# schematic.net
KiCad netlist of a schematic drawn in Altium Designer
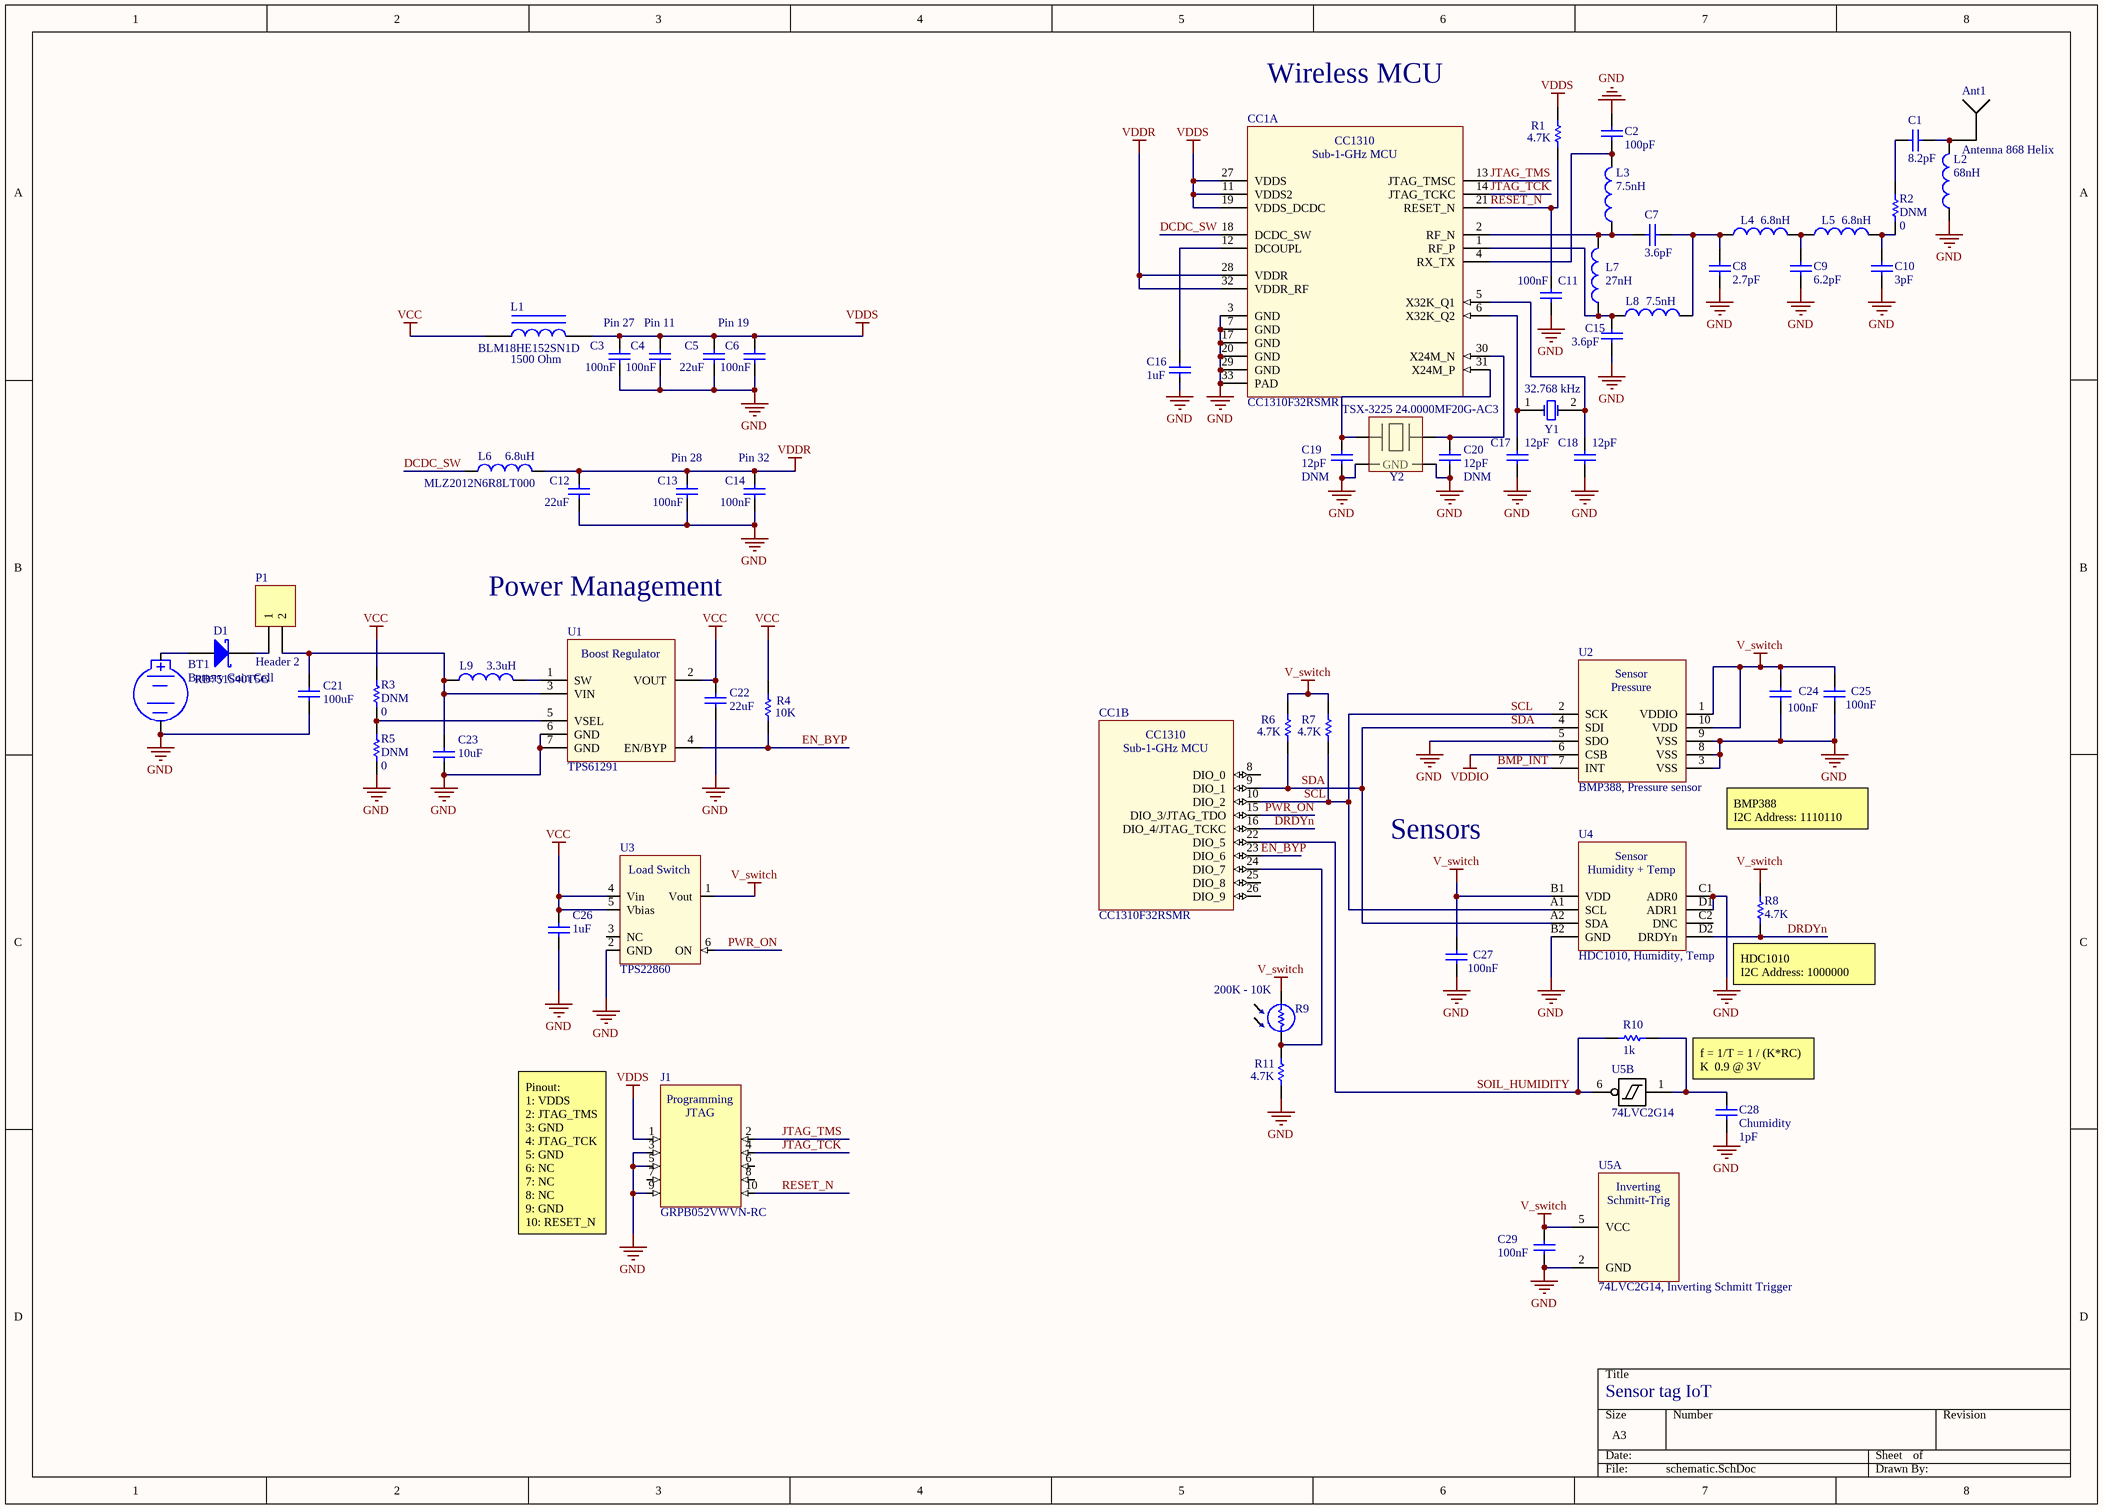
[diagram p0: schematic.SchDoc]

(export (version "E")
  (design (tool "Eeschema 10.0.6"))
  (components
    (comp (ref "Ant1")
      (value "Antenna 868 Helix")
      (footprint "Antenna_868_Helix")
      (libsource (lib "components") (part "Antenna 868 Helix"))
    )
    (comp (ref "BT1")
      (value "Battery Coin Cell")
      (footprint "S8421-45R")
      (libsource (lib "components") (part "Battery Coin Cell"))
    )
    (comp (ref "C1")
      (value "8.2pF")
      (footprint "0402 (CAP)")
      (description "Capacitor")
      (fields (field (name "Comment") "Cap") (field (name "PUBLISHER") "Altium Limited"))
      (libsource (lib "Miscellaneous Devices") (part "Cap"))
    )
    (comp (ref "C2")
      (value "100pF")
      (footprint "0402 (CAP)")
      (description "Capacitor")
      (fields (field (name "Comment") "Cap") (field (name "PUBLISHER") "Altium Limited"))
      (libsource (lib "Miscellaneous Devices") (part "Cap"))
    )
    (comp (ref "C3")
      (value "100nF")
      (footprint "0402 (CAP)")
      (description "Capacitor")
      (fields (field (name "Comment") "Cap") (field (name "PUBLISHER") "Altium Limited"))
      (libsource (lib "Miscellaneous Devices") (part "Cap"))
    )
    (comp (ref "C4")
      (value "100nF")
      (footprint "0402 (CAP)")
      (description "Capacitor")
      (fields (field (name "Comment") "Cap") (field (name "PUBLISHER") "Altium Limited"))
      (libsource (lib "Miscellaneous Devices") (part "Cap"))
    )
    (comp (ref "C5")
      (value "22uF")
      (footprint "0402 (CAP)")
      (description "Capacitor")
      (fields (field (name "Comment") "Cap") (field (name "PUBLISHER") "Altium Limited"))
      (libsource (lib "Miscellaneous Devices") (part "Cap"))
    )
    (comp (ref "C6")
      (value "100nF")
      (footprint "0402 (CAP)")
      (description "Capacitor")
      (fields (field (name "Comment") "Cap") (field (name "PUBLISHER") "Altium Limited"))
      (libsource (lib "Miscellaneous Devices") (part "Cap"))
    )
    (comp (ref "C7")
      (value "3.6pF")
      (footprint "0402 (CAP)")
      (description "Capacitor")
      (fields (field (name "Comment") "Cap") (field (name "PUBLISHER") "Altium Limited"))
      (libsource (lib "Miscellaneous Devices") (part "Cap"))
    )
    (comp (ref "C8")
      (value "2.7pF")
      (footprint "0402 (CAP)")
      (description "Capacitor")
      (fields (field (name "Comment") "Cap") (field (name "PUBLISHER") "Altium Limited"))
      (libsource (lib "Miscellaneous Devices") (part "Cap"))
    )
    (comp (ref "C9")
      (value "6.2pF")
      (footprint "0402 (CAP)")
      (description "Capacitor")
      (fields (field (name "Comment") "Cap") (field (name "PUBLISHER") "Altium Limited"))
      (libsource (lib "Miscellaneous Devices") (part "Cap"))
    )
    (comp (ref "C10")
      (value "3pF")
      (footprint "0402 (CAP)")
      (description "Capacitor")
      (fields (field (name "Comment") "Cap") (field (name "PUBLISHER") "Altium Limited"))
      (libsource (lib "Miscellaneous Devices") (part "Cap"))
    )
    (comp (ref "C11")
      (value "100nF")
      (footprint "0402 (CAP)")
      (description "Capacitor")
      (fields (field (name "Comment") "Cap") (field (name "PUBLISHER") "Altium Limited"))
      (libsource (lib "Miscellaneous Devices") (part "Cap"))
    )
    (comp (ref "C12")
      (value "22uF")
      (footprint "0402 (CAP)")
      (description "Capacitor")
      (fields (field (name "Comment") "Cap") (field (name "PUBLISHER") "Altium Limited"))
      (libsource (lib "Miscellaneous Devices") (part "Cap"))
    )
    (comp (ref "C13")
      (value "100nF")
      (footprint "0402 (CAP)")
      (description "Capacitor")
      (fields (field (name "Comment") "Cap") (field (name "PUBLISHER") "Altium Limited"))
      (libsource (lib "Miscellaneous Devices") (part "Cap"))
    )
    (comp (ref "C14")
      (value "100nF")
      (footprint "0402 (CAP)")
      (description "Capacitor")
      (fields (field (name "Comment") "Cap") (field (name "PUBLISHER") "Altium Limited"))
      (libsource (lib "Miscellaneous Devices") (part "Cap"))
    )
    (comp (ref "C15")
      (value "3.6pF")
      (footprint "0402 (CAP)")
      (description "Capacitor")
      (fields (field (name "Comment") "Cap") (field (name "PUBLISHER") "Altium Limited"))
      (libsource (lib "Miscellaneous Devices") (part "Cap"))
    )
    (comp (ref "C16")
      (value "1uF")
      (footprint "0402 (CAP)")
      (description "Capacitor")
      (fields (field (name "Comment") "Cap") (field (name "PUBLISHER") "Altium Limited"))
      (libsource (lib "Miscellaneous Devices") (part "Cap"))
    )
    (comp (ref "C17")
      (value "12pF")
      (footprint "0402 (CAP)")
      (description "Capacitor")
      (fields (field (name "Comment") "Cap") (field (name "PUBLISHER") "Altium Limited"))
      (libsource (lib "Miscellaneous Devices") (part "Cap"))
    )
    (comp (ref "C18")
      (value "12pF")
      (footprint "0402 (CAP)")
      (description "Capacitor")
      (fields (field (name "Comment") "Cap") (field (name "PUBLISHER") "Altium Limited"))
      (libsource (lib "Miscellaneous Devices") (part "Cap"))
    )
    (comp (ref "C19")
      (value "DNM")
      (footprint "0402 (CAP)")
      (description "Capacitor")
      (fields (field (name "ALTIUM_VALUE") "12pF") (field (name "PUBLISHER") "Altium Limited"))
      (libsource (lib "Miscellaneous Devices") (part "Cap"))
    )
    (comp (ref "C20")
      (value "DNM")
      (footprint "0402 (CAP)")
      (description "Capacitor")
      (fields (field (name "ALTIUM_VALUE") "12pF") (field (name "PUBLISHER") "Altium Limited"))
      (libsource (lib "Miscellaneous Devices") (part "Cap"))
    )
    (comp (ref "C21")
      (value "100uF")
      (footprint "1210 (CAP)")
      (description "Capacitor")
      (fields (field (name "Comment") "GRM32EC70J107ME15L") (field (name "PUBLISHER") "Altium Limited"))
      (libsource (lib "Miscellaneous Devices") (part "Cap"))
    )
    (comp (ref "C22")
      (value "22uF")
      (footprint "0805 (CAP)")
      (description "Capacitor")
      (fields (field (name "Comment") "Cap") (field (name "PUBLISHER") "Altium Limited"))
      (libsource (lib "Miscellaneous Devices") (part "Cap"))
    )
    (comp (ref "C23")
      (value "10uF")
      (footprint "0805 (CAP)")
      (description "Capacitor")
      (fields (field (name "Comment") "Cap") (field (name "PUBLISHER") "Altium Limited"))
      (libsource (lib "Miscellaneous Devices") (part "Cap"))
    )
    (comp (ref "C24")
      (value "100nF")
      (footprint "0402 (CAP)")
      (description "Capacitor")
      (fields (field (name "Comment") "Cap") (field (name "PUBLISHER") "Altium Limited"))
      (libsource (lib "Miscellaneous Devices") (part "Cap"))
    )
    (comp (ref "C25")
      (value "100nF")
      (footprint "0402 (CAP)")
      (description "Capacitor")
      (fields (field (name "Comment") "Cap") (field (name "PUBLISHER") "Altium Limited"))
      (libsource (lib "Miscellaneous Devices") (part "Cap"))
    )
    (comp (ref "C26")
      (value "1uF")
      (footprint "0402 (CAP)")
      (description "Capacitor")
      (fields (field (name "Comment") "Cap") (field (name "PUBLISHER") "Altium Limited"))
      (libsource (lib "Miscellaneous Devices") (part "Cap"))
    )
    (comp (ref "C27")
      (value "100nF")
      (footprint "0402 (CAP)")
      (description "Capacitor")
      (fields (field (name "Comment") "Cap") (field (name "PUBLISHER") "Altium Limited"))
      (libsource (lib "Miscellaneous Devices") (part "Cap"))
    )
    (comp (ref "C28")
      (value "Chumidity")
      (footprint "Soil_Cap")
      (description "Capacitor")
      (fields (field (name "ALTIUM_VALUE") "1pF") (field (name "PUBLISHER") "Altium Limited"))
      (libsource (lib "Miscellaneous Devices") (part "Cap"))
    )
    (comp (ref "C29")
      (value "100nF")
      (footprint "0402 (CAP)")
      (description "Capacitor")
      (fields (field (name "Comment") "Cap") (field (name "PUBLISHER") "Altium Limited"))
      (libsource (lib "Miscellaneous Devices") (part "Cap"))
    )
    (comp (ref "CC1")
      (value "CC1310F32RSMR")
      (footprint "CC1310F32RSMR")
      (libsource (lib "components") (part "CC1310F32RSMR"))
    )
    (comp (ref "D1")
      (value "RB751S40T5G")
      (footprint "SOD-523")
      (description "Schottky Diode")
      (fields (field (name "PUBLISHER") "Altium Limited"))
      (libsource (lib "Miscellaneous Devices") (part "D Schottky"))
    )
    (comp (ref "J1") (value "GRPB052VWVN-RC") (libsource (lib "connectors") (part "GRPB052VWVN-RC")))
    (comp (ref "L1")
      (value "BLM18HE152SN1D")
      (footprint "0603 (IND)")
      (description "Magnetic-Core Inductor")
      (fields (field (name "ALTIUM_VALUE") "1500 Ohm") (field (name "PUBLISHER") "Altium Limited"))
      (libsource (lib "Miscellaneous Devices") (part "Inductor Iron"))
    )
    (comp (ref "L2")
      (value "68nH")
      (footprint "0603 (IND)")
      (description "Inductor")
      (fields (field (name "PUBLISHER") "Altium Limited"))
      (libsource (lib "Miscellaneous Devices") (part "Inductor"))
    )
    (comp (ref "L3")
      (value "7.5nH")
      (footprint "0402 (IND)")
      (description "Inductor")
      (fields (field (name "PUBLISHER") "Altium Limited"))
      (libsource (lib "") (part "Inductor_1"))
    )
    (comp (ref "L4")
      (value "6.8nH")
      (footprint "LQW15AN6N8G00D")
      (description "Inductor")
      (fields (field (name "PUBLISHER") "Altium Limited"))
      (libsource (lib "Miscellaneous Devices") (part "Inductor"))
    )
    (comp (ref "L5")
      (value "6.8nH")
      (footprint "LQW15AN6N8G00D")
      (description "Inductor")
      (fields (field (name "PUBLISHER") "Altium Limited"))
      (libsource (lib "Miscellaneous Devices") (part "Inductor"))
    )
    (comp (ref "L6")
      (value "MLZ2012N6R8LT000")
      (footprint "0805 (IND)")
      (description "Inductor")
      (fields (field (name "ALTIUM_VALUE") "6.8uH") (field (name "PUBLISHER") "Altium Limited"))
      (libsource (lib "") (part "Inductor_1"))
    )
    (comp (ref "L7")
      (value "27nH")
      (footprint "0402 (IND)")
      (description "Inductor")
      (fields (field (name "PUBLISHER") "Altium Limited"))
      (libsource (lib "Miscellaneous Devices") (part "Inductor"))
    )
    (comp (ref "L8")
      (value "7.5nH")
      (footprint "0402 (IND)")
      (description "Inductor")
      (fields (field (name "PUBLISHER") "Altium Limited"))
      (libsource (lib "Miscellaneous Devices") (part "Inductor"))
    )
    (comp (ref "L9")
      (value "3.3uH")
      (footprint "SRN2009T")
      (description "Inductor")
      (fields (field (name "PUBLISHER") "Altium Limited"))
      (libsource (lib "") (part "Inductor_1"))
    )
    (comp (ref "P1")
      (value "Header 2")
      (footprint "HDR1X2")
      (description "Header, 2-Pin")
      (fields (field (name "PUBLISHER") "Altium Limited"))
      (libsource (lib "Miscellaneous Connectors") (part "Header 2"))
    )
    (comp (ref "R1")
      (value "4.7K")
      (footprint "0402 (RES)")
      (description "Resistor")
      (fields (field (name "Comment") "Res1") (field (name "PUBLISHER") "Altium Limited"))
      (libsource (lib "Miscellaneous Devices") (part "Res1"))
    )
    (comp (ref "R2")
      (value "DNM")
      (footprint "0402 (RES)")
      (description "Resistor")
      (fields (field (name "ALTIUM_VALUE") "0") (field (name "PUBLISHER") "Altium Limited"))
      (libsource (lib "Miscellaneous Devices") (part "Res1"))
    )
    (comp (ref "R3")
      (value "DNM")
      (footprint "0402 (RES)")
      (description "Resistor")
      (fields (field (name "ALTIUM_VALUE") "0") (field (name "PUBLISHER") "Altium Limited"))
      (libsource (lib "Miscellaneous Devices") (part "Res1"))
    )
    (comp (ref "R4")
      (value "10K")
      (footprint "0402 (RES)")
      (description "Resistor")
      (fields (field (name "Comment") "Res1") (field (name "PUBLISHER") "Altium Limited"))
      (libsource (lib "Miscellaneous Devices") (part "Res1"))
    )
    (comp (ref "R5")
      (value "DNM")
      (footprint "0402 (RES)")
      (description "Resistor")
      (fields (field (name "ALTIUM_VALUE") "0") (field (name "PUBLISHER") "Altium Limited"))
      (libsource (lib "Miscellaneous Devices") (part "Res1"))
    )
    (comp (ref "R6")
      (value "4.7K")
      (footprint "0402 (RES)")
      (description "Resistor")
      (fields (field (name "Comment") "Res1") (field (name "PUBLISHER") "Altium Limited"))
      (libsource (lib "Miscellaneous Devices") (part "Res1"))
    )
    (comp (ref "R7")
      (value "4.7K")
      (footprint "0402 (RES)")
      (description "Resistor")
      (fields (field (name "Comment") "Res1") (field (name "PUBLISHER") "Altium Limited"))
      (libsource (lib "Miscellaneous Devices") (part "Res1"))
    )
    (comp (ref "R8")
      (value "4.7K")
      (footprint "0402 (RES)")
      (description "Resistor")
      (fields (field (name "Comment") "Res1") (field (name "PUBLISHER") "Altium Limited"))
      (libsource (lib "Miscellaneous Devices") (part "Res1"))
    )
    (comp (ref "R9")
      (value "200K - 10K")
      (footprint "Photoresistor")
      (libsource (lib "components") (part "Photo Resistor"))
    )
    (comp (ref "R10")
      (value "1k")
      (footprint "0402 (RES)")
      (description "Resistor")
      (fields (field (name "Comment") "Rcharge") (field (name "PUBLISHER") "Altium Limited"))
      (libsource (lib "Miscellaneous Devices") (part "Res1"))
    )
    (comp (ref "R11")
      (value "4.7K")
      (footprint "0402 (RES)")
      (description "Resistor")
      (fields (field (name "Comment") "Res1") (field (name "PUBLISHER") "Altium Limited"))
      (libsource (lib "Miscellaneous Devices") (part "Res1"))
    )
    (comp (ref "U1")
      (value "TPS61291")
      (footprint "TPS61291")
      (libsource (lib "components") (part "TPS61291"))
    )
    (comp (ref "U2")
      (value "BMP388, Pressure sensor")
      (footprint "BMP388")
      (libsource (lib "components") (part "BMP388"))
    )
    (comp (ref "U3")
      (value "TPS22860")
      (footprint "SOT23-5")
      (libsource (lib "components") (part "TPS22860"))
    )
    (comp (ref "U4")
      (value "HDC1010, Humidity, Temp")
      (footprint "HDC1010")
      (libsource (lib "components") (part "HDC1010"))
    )
    (comp (ref "U5")
      (value "74LVC2G14, Inverting Schmitt Trigger")
      (footprint "74LVC2G14")
      (libsource (lib "components") (part "74LVC2G14"))
    )
    (comp (ref "Y1")
      (value "32.768 kHz")
      (footprint "FC-12M 32.7680KA-A3")
      (description "Crystal Oscillator")
      (fields (field (name "PUBLISHER") "Altium Limited"))
      (libsource (lib "Miscellaneous Devices") (part "XTAL"))
    )
    (comp (ref "Y2")
      (value "TSX-3225 24.0000MF20G-AC3")
      (footprint "TSX-3225 24.0000MF20G-AC3")
      (libsource (lib "components") (part "Crystal"))
    )
  )
  (nets
    (net (code "1") (name "/BMP_INT") (class "Default")
      (node (ref "U2") (pin "7") (pinfunction "INT_7") (pintype "passive"))
    )
    (net (code "2") (name "/DCDC_SW") (class "Default")
      (node (ref "CC1") (pin "18") (pinfunction "DCDC_SW_18") (pintype "power_in"))
      (node (ref "L6") (pin "1") (pinfunction "1_1") (pintype "passive"))
    )
    (net (code "3") (name "/DRDYn") (class "Default")
      (node (ref "CC1") (pin "16") (pinfunction "DIO_4/JTAG_TCKC_16") (pintype "bidirectional"))
      (node (ref "R8") (pin "2") (pinfunction "2_2") (pintype "passive"))
      (node (ref "U4") (pin "D2") (pinfunction "DRDYn_D2") (pintype "passive"))
    )
    (net (code "4") (name "/EN_BYP") (class "Default")
      (node (ref "CC1") (pin "23") (pinfunction "DIO_6_23") (pintype "bidirectional"))
      (node (ref "R4") (pin "2") (pinfunction "2_2") (pintype "passive"))
      (node (ref "U1") (pin "4") (pinfunction "EN/BYP_4") (pintype "passive"))
    )
    (net (code "5") (name "/JTAG_TCK") (class "Default")
      (node (ref "CC1") (pin "14") (pinfunction "JTAG_TCKC_14") (pintype "passive"))
      (node (ref "J1") (pin "4") (pinfunction "JTAG_TCK_4") (pintype "input"))
    )
    (net (code "6") (name "/JTAG_TMS") (class "Default")
      (node (ref "CC1") (pin "13") (pinfunction "JTAG_TMSC_13") (pintype "passive"))
      (node (ref "J1") (pin "2") (pinfunction "JTAG_TMS_2") (pintype "input"))
    )
    (net (code "7") (name "/PWR_ON") (class "Default")
      (node (ref "CC1") (pin "15") (pinfunction "DIO_3/JTAG_TDO_15") (pintype "bidirectional"))
      (node (ref "U3") (pin "6") (pinfunction "ON_6") (pintype "input"))
    )
    (net (code "8") (name "/RESET_N") (class "Default")
      (node (ref "C11") (pin "1") (pinfunction "1_1") (pintype "passive"))
      (node (ref "CC1") (pin "21") (pinfunction "RESET_N_21") (pintype "passive"))
      (node (ref "J1") (pin "10") (pinfunction "RESET_N_10") (pintype "input"))
      (node (ref "R1") (pin "1") (pinfunction "1_1") (pintype "passive"))
    )
    (net (code "9") (name "/SCL") (class "Default")
      (node (ref "CC1") (pin "10") (pinfunction "DIO_2_10") (pintype "bidirectional"))
      (node (ref "R7") (pin "1") (pinfunction "1_1") (pintype "passive"))
      (node (ref "U2") (pin "2") (pinfunction "SCK_2") (pintype "passive"))
      (node (ref "U4") (pin "A1") (pinfunction "SCL_A1") (pintype "passive"))
    )
    (net (code "10") (name "/SDA") (class "Default")
      (node (ref "CC1") (pin "9") (pinfunction "DIO_1_9") (pintype "bidirectional"))
      (node (ref "R6") (pin "1") (pinfunction "1_1") (pintype "passive"))
      (node (ref "U2") (pin "4") (pinfunction "SDI_4") (pintype "passive"))
      (node (ref "U4") (pin "A2") (pinfunction "SDA_A2") (pintype "passive"))
    )
    (net (code "11") (name "/SOIL_HUMIDITY") (class "Default")
      (node (ref "CC1") (pin "22") (pinfunction "DIO_5_22") (pintype "bidirectional"))
      (node (ref "R10") (pin "2") (pinfunction "2_2") (pintype "passive"))
      (node (ref "U5") (pin "6") (pinfunction "1Y_6") (pintype "passive"))
    )
    (net (code "12") (name "GND") (class "Default")
      (node (ref "BT1") (pin "2") (pinfunction "Negative_2") (pintype "passive"))
      (node (ref "C10") (pin "2") (pinfunction "2_2") (pintype "passive"))
      (node (ref "C11") (pin "2") (pinfunction "2_2") (pintype "passive"))
      (node (ref "C12") (pin "1") (pinfunction "1_1") (pintype "passive"))
      (node (ref "C13") (pin "1") (pinfunction "1_1") (pintype "passive"))
      (node (ref "C14") (pin "1") (pinfunction "1_1") (pintype "passive"))
      (node (ref "C15") (pin "2") (pinfunction "2_2") (pintype "passive"))
      (node (ref "C16") (pin "1") (pinfunction "1_1") (pintype "passive"))
      (node (ref "C17") (pin "1") (pinfunction "1_1") (pintype "passive"))
      (node (ref "C18") (pin "1") (pinfunction "1_1") (pintype "passive"))
      (node (ref "C19") (pin "1") (pinfunction "1_1") (pintype "passive"))
      (node (ref "C2") (pin "1") (pinfunction "1_1") (pintype "passive"))
      (node (ref "C20") (pin "1") (pinfunction "1_1") (pintype "passive"))
      (node (ref "C21") (pin "1") (pinfunction "1_1") (pintype "passive"))
      (node (ref "C22") (pin "1") (pinfunction "1_1") (pintype "passive"))
      (node (ref "C23") (pin "1") (pinfunction "1_1") (pintype "passive"))
      (node (ref "C24") (pin "1") (pinfunction "1_1") (pintype "passive"))
      (node (ref "C25") (pin "1") (pinfunction "1_1") (pintype "passive"))
      (node (ref "C26") (pin "1") (pinfunction "1_1") (pintype "passive"))
      (node (ref "C27") (pin "1") (pinfunction "1_1") (pintype "passive"))
      (node (ref "C28") (pin "2") (pinfunction "2_2") (pintype "passive"))
      (node (ref "C29") (pin "1") (pinfunction "1_1") (pintype "passive"))
      (node (ref "C3") (pin "1") (pinfunction "1_1") (pintype "passive"))
      (node (ref "C4") (pin "1") (pinfunction "1_1") (pintype "passive"))
      (node (ref "C5") (pin "1") (pinfunction "1_1") (pintype "passive"))
      (node (ref "C6") (pin "1") (pinfunction "1_1") (pintype "passive"))
      (node (ref "C8") (pin "2") (pinfunction "2_2") (pintype "passive"))
      (node (ref "C9") (pin "2") (pinfunction "2_2") (pintype "passive"))
      (node (ref "CC1") (pin "17") (pinfunction "GND_17") (pintype "passive"))
      (node (ref "CC1") (pin "20") (pinfunction "GND_20") (pintype "passive"))
      (node (ref "CC1") (pin "29") (pinfunction "GND_29") (pintype "passive"))
      (node (ref "CC1") (pin "3") (pinfunction "GND_3") (pintype "passive"))
      (node (ref "CC1") (pin "33") (pinfunction "PAD_33") (pintype "passive"))
      (node (ref "CC1") (pin "7") (pinfunction "GND_7") (pintype "passive"))
      (node (ref "J1") (pin "3") (pinfunction "GND_3") (pintype "input"))
      (node (ref "J1") (pin "5") (pinfunction "GND_5") (pintype "input"))
      (node (ref "J1") (pin "9") (pinfunction "GND_9") (pintype "input"))
      (node (ref "L2") (pin "2") (pinfunction "2_2") (pintype "passive"))
      (node (ref "R11") (pin "1") (pinfunction "1_1") (pintype "passive"))
      (node (ref "R5") (pin "2") (pinfunction "2_2") (pintype "passive"))
      (node (ref "U1") (pin "6") (pinfunction "GND_6") (pintype "passive"))
      (node (ref "U1") (pin "7") (pinfunction "GND_7") (pintype "passive"))
      (node (ref "U2") (pin "3") (pinfunction "VSS_3") (pintype "passive"))
      (node (ref "U2") (pin "5") (pinfunction "SDO_5") (pintype "passive"))
      (node (ref "U2") (pin "8") (pinfunction "VSS_8") (pintype "passive"))
      (node (ref "U2") (pin "9") (pinfunction "VSS_9") (pintype "passive"))
      (node (ref "U3") (pin "2") (pinfunction "GND_2") (pintype "power_in"))
      (node (ref "U4") (pin "B2") (pinfunction "GND_B2") (pintype "passive"))
      (node (ref "U4") (pin "C1") (pinfunction "ADR0_C1") (pintype "passive"))
      (node (ref "U4") (pin "D1") (pinfunction "ADR1_D1") (pintype "passive"))
      (node (ref "U5") (pin "2") (pinfunction "GND_2") (pintype "passive"))
      (node (ref "Y2") (pin "2") (pinfunction "ON_2") (pintype "passive"))
      (node (ref "Y2") (pin "4") (pinfunction "ON_4") (pintype "passive"))
    )
    (net (code "13") (name "Net-(Ant1-0)") (class "Default")
      (node (ref "Ant1") (pin "1") (pinfunction "0_1") (pintype "passive"))
      (node (ref "C1") (pin "2") (pinfunction "2_2") (pintype "passive"))
      (node (ref "L2") (pin "1") (pinfunction "1_1") (pintype "passive"))
    )
    (net (code "14") (name "Net-(BT1-Positive)") (class "Default")
      (node (ref "BT1") (pin "1") (pinfunction "Positive_1") (pintype "passive"))
      (node (ref "D1") (pin "1") (pinfunction "A_1") (pintype "passive"))
    )
    (net (code "15") (name "Net-(C1-Pad1)") (class "Default")
      (node (ref "C1") (pin "1") (pinfunction "1_1") (pintype "passive"))
      (node (ref "R2") (pin "1") (pinfunction "1_1") (pintype "passive"))
    )
    (net (code "16") (name "Net-(C7-Pad2)") (class "Default")
      (node (ref "C7") (pin "2") (pinfunction "2_2") (pintype "passive"))
      (node (ref "C8") (pin "1") (pinfunction "1_1") (pintype "passive"))
      (node (ref "L4") (pin "2") (pinfunction "2_2") (pintype "passive"))
      (node (ref "L8") (pin "1") (pinfunction "1_1") (pintype "passive"))
    )
    (net (code "17") (name "Net-(C9-Pad1)") (class "Default")
      (node (ref "C9") (pin "1") (pinfunction "1_1") (pintype "passive"))
      (node (ref "L4") (pin "1") (pinfunction "1_1") (pintype "passive"))
      (node (ref "L5") (pin "2") (pinfunction "2_2") (pintype "passive"))
    )
    (net (code "18") (name "Net-(C10-Pad1)") (class "Default")
      (node (ref "C10") (pin "1") (pinfunction "1_1") (pintype "passive"))
      (node (ref "L5") (pin "1") (pinfunction "1_1") (pintype "passive"))
      (node (ref "R2") (pin "2") (pinfunction "2_2") (pintype "passive"))
    )
    (net (code "19") (name "Net-(CC1A-DCOUPL)") (class "Default")
      (node (ref "C16") (pin "2") (pinfunction "2_2") (pintype "passive"))
      (node (ref "CC1") (pin "12") (pinfunction "DCOUPL_12") (pintype "power_in"))
    )
    (net (code "20") (name "Net-(CC1A-RF_N)") (class "Default")
      (node (ref "C7") (pin "1") (pinfunction "1_1") (pintype "passive"))
      (node (ref "CC1") (pin "2") (pinfunction "RF_N_2") (pintype "passive"))
      (node (ref "L3") (pin "1") (pinfunction "1_1") (pintype "passive"))
      (node (ref "L7") (pin "1") (pinfunction "1_1") (pintype "passive"))
    )
    (net (code "21") (name "Net-(CC1A-RF_P)") (class "Default")
      (node (ref "C15") (pin "1") (pinfunction "1_1") (pintype "passive"))
      (node (ref "CC1") (pin "1") (pinfunction "RF_P_1") (pintype "passive"))
      (node (ref "L7") (pin "2") (pinfunction "2_2") (pintype "passive"))
      (node (ref "L8") (pin "2") (pinfunction "2_2") (pintype "passive"))
    )
    (net (code "22") (name "Net-(CC1A-RX_TX)") (class "Default")
      (node (ref "C2") (pin "2") (pinfunction "2_2") (pintype "passive"))
      (node (ref "CC1") (pin "4") (pinfunction "RX_TX_4") (pintype "passive"))
      (node (ref "L3") (pin "2") (pinfunction "2_2") (pintype "passive"))
    )
    (net (code "23") (name "Net-(CC1A-X24M_N)") (class "Default")
      (node (ref "C20") (pin "2") (pinfunction "2_2") (pintype "passive"))
      (node (ref "CC1") (pin "30") (pinfunction "X24M_N_30") (pintype "input"))
      (node (ref "Y2") (pin "3") (pinfunction "ON_3") (pintype "passive"))
    )
    (net (code "24") (name "Net-(CC1A-X24M_P)") (class "Default")
      (node (ref "C19") (pin "2") (pinfunction "2_2") (pintype "passive"))
      (node (ref "CC1") (pin "31") (pinfunction "X24M_P_31") (pintype "input"))
      (node (ref "Y2") (pin "1") (pinfunction "ON_1") (pintype "passive"))
    )
    (net (code "25") (name "Net-(CC1A-X32K_Q1)") (class "Default")
      (node (ref "C18") (pin "2") (pinfunction "2_2") (pintype "passive"))
      (node (ref "CC1") (pin "5") (pinfunction "X32K_Q1_5") (pintype "input"))
      (node (ref "Y1") (pin "2") (pinfunction "OSC2_2") (pintype "passive"))
    )
    (net (code "26") (name "Net-(CC1A-X32K_Q2)") (class "Default")
      (node (ref "C17") (pin "2") (pinfunction "2_2") (pintype "passive"))
      (node (ref "CC1") (pin "6") (pinfunction "X32K_Q2_6") (pintype "input"))
      (node (ref "Y1") (pin "1") (pinfunction "OSC1_1") (pintype "passive"))
    )
    (net (code "27") (name "Net-(CC1B-DIO_7)") (class "Default")
      (node (ref "CC1") (pin "24") (pinfunction "DIO_7_24") (pintype "bidirectional"))
      (node (ref "R11") (pin "2") (pinfunction "2_2") (pintype "passive"))
      (node (ref "R9") (pin "2") (pinfunction "2_2") (pintype "passive"))
    )
    (net (code "28") (name "Net-(D1-K)") (class "Default")
      (node (ref "D1") (pin "2") (pinfunction "K_2") (pintype "passive"))
      (node (ref "P1") (pin "1") (pinfunction "1_1") (pintype "passive"))
    )
    (net (code "29") (name "Net-(U1-SW)") (class "Default")
      (node (ref "L9") (pin "2") (pinfunction "2_2") (pintype "passive"))
      (node (ref "U1") (pin "1") (pinfunction "SW_1") (pintype "passive"))
    )
    (net (code "30") (name "Net-(U1-VIN)") (class "Default")
      (node (ref "C21") (pin "2") (pinfunction "2_2") (pintype "passive"))
      (node (ref "C23") (pin "2") (pinfunction "2_2") (pintype "passive"))
      (node (ref "L9") (pin "1") (pinfunction "1_1") (pintype "passive"))
      (node (ref "P1") (pin "2") (pinfunction "2_2") (pintype "passive"))
      (node (ref "U1") (pin "3") (pinfunction "VIN_3") (pintype "passive"))
    )
    (net (code "31") (name "Net-(U1-VSEL)") (class "Default")
      (node (ref "R3") (pin "2") (pinfunction "2_2") (pintype "passive"))
      (node (ref "R5") (pin "1") (pinfunction "1_1") (pintype "passive"))
      (node (ref "U1") (pin "5") (pinfunction "VSEL_5") (pintype "passive"))
    )
    (net (code "32") (name "Net-(U5B-1A)") (class "Default")
      (node (ref "C28") (pin "1") (pinfunction "1_1") (pintype "passive"))
      (node (ref "R10") (pin "1") (pinfunction "1_1") (pintype "passive"))
      (node (ref "U5") (pin "1") (pinfunction "1A_1") (pintype "passive"))
    )
    (net (code "33") (name "VCC") (class "Default")
      (node (ref "C22") (pin "2") (pinfunction "2_2") (pintype "passive"))
      (node (ref "C26") (pin "2") (pinfunction "2_2") (pintype "passive"))
      (node (ref "L1") (pin "1") (pinfunction "1_1") (pintype "passive"))
      (node (ref "R3") (pin "1") (pinfunction "1_1") (pintype "passive"))
      (node (ref "R4") (pin "1") (pinfunction "1_1") (pintype "passive"))
      (node (ref "U1") (pin "2") (pinfunction "VOUT_2") (pintype "passive"))
      (node (ref "U3") (pin "4") (pinfunction "Vin_4") (pintype "power_in"))
      (node (ref "U3") (pin "5") (pinfunction "Vbias_5") (pintype "power_in"))
    )
    (net (code "34") (name "VDDIO") (class "Default")
      (node (ref "U2") (pin "6") (pinfunction "CSB_6") (pintype "passive"))
    )
    (net (code "35") (name "VDDR") (class "Default")
      (node (ref "C12") (pin "2") (pinfunction "2_2") (pintype "passive"))
      (node (ref "C13") (pin "2") (pinfunction "2_2") (pintype "passive"))
      (node (ref "C14") (pin "2") (pinfunction "2_2") (pintype "passive"))
      (node (ref "CC1") (pin "28") (pinfunction "VDDR_28") (pintype "power_in"))
      (node (ref "CC1") (pin "32") (pinfunction "VDDR_RF_32") (pintype "power_in"))
      (node (ref "L6") (pin "2") (pinfunction "2_2") (pintype "passive"))
    )
    (net (code "36") (name "VDDS") (class "Default")
      (node (ref "C3") (pin "2") (pinfunction "2_2") (pintype "passive"))
      (node (ref "C4") (pin "2") (pinfunction "2_2") (pintype "passive"))
      (node (ref "C5") (pin "2") (pinfunction "2_2") (pintype "passive"))
      (node (ref "C6") (pin "2") (pinfunction "2_2") (pintype "passive"))
      (node (ref "CC1") (pin "11") (pinfunction "VDDS2_11") (pintype "passive"))
      (node (ref "CC1") (pin "19") (pinfunction "VDDS_DCDC_19") (pintype "passive"))
      (node (ref "CC1") (pin "27") (pinfunction "VDDS_27") (pintype "passive"))
      (node (ref "J1") (pin "1") (pinfunction "VDDS_1") (pintype "input"))
      (node (ref "L1") (pin "2") (pinfunction "2_2") (pintype "passive"))
      (node (ref "R1") (pin "2") (pinfunction "2_2") (pintype "passive"))
    )
    (net (code "37") (name "V_switch") (class "Default")
      (node (ref "C24") (pin "2") (pinfunction "2_2") (pintype "passive"))
      (node (ref "C25") (pin "2") (pinfunction "2_2") (pintype "passive"))
      (node (ref "C27") (pin "2") (pinfunction "2_2") (pintype "passive"))
      (node (ref "C29") (pin "2") (pinfunction "2_2") (pintype "passive"))
      (node (ref "R6") (pin "2") (pinfunction "2_2") (pintype "passive"))
      (node (ref "R7") (pin "2") (pinfunction "2_2") (pintype "passive"))
      (node (ref "R8") (pin "1") (pinfunction "1_1") (pintype "passive"))
      (node (ref "R9") (pin "1") (pinfunction "1_1") (pintype "passive"))
      (node (ref "U2") (pin "1") (pinfunction "VDDIO_1") (pintype "passive"))
      (node (ref "U2") (pin "10") (pinfunction "VDD_10") (pintype "passive"))
      (node (ref "U3") (pin "1") (pinfunction "Vout_1") (pintype "power_in"))
      (node (ref "U4") (pin "B1") (pinfunction "VDD_B1") (pintype "passive"))
      (node (ref "U5") (pin "5") (pinfunction "VCC_5") (pintype "passive"))
    )
    (net (code "38") (name "unconnected-(CC1B-DIO_0-Pad8)") (class "Default")
      (node (ref "CC1") (pin "8") (pinfunction "DIO_0_8") (pintype "bidirectional"))
    )
    (net (code "39") (name "unconnected-(CC1B-DIO_8-Pad25)") (class "Default")
      (node (ref "CC1") (pin "25") (pinfunction "DIO_8_25") (pintype "bidirectional"))
    )
    (net (code "40") (name "unconnected-(CC1B-DIO_9-Pad26)") (class "Default")
      (node (ref "CC1") (pin "26") (pinfunction "DIO_9_26") (pintype "bidirectional"))
    )
    (net (code "41") (name "unconnected-(J1-NC-Pad6)") (class "Default")
      (node (ref "J1") (pin "6") (pinfunction "NC_6") (pintype "input"))
    )
    (net (code "42") (name "unconnected-(J1-NC-Pad7)") (class "Default")
      (node (ref "J1") (pin "7") (pinfunction "NC_7") (pintype "input"))
    )
    (net (code "43") (name "unconnected-(J1-NC-Pad8)") (class "Default")
      (node (ref "J1") (pin "8") (pinfunction "NC_8") (pintype "input"))
    )
    (net (code "44") (name "unconnected-(U3-NC-Pad3)") (class "Default")
      (node (ref "U3") (pin "3") (pinfunction "NC_3") (pintype "passive"))
    )
    (net (code "45") (name "unconnected-(U4-DNC-PadC2)") (class "Default")
      (node (ref "U4") (pin "C2") (pinfunction "DNC_C2") (pintype "passive"))
    )
  )
)
